# Dual_H-Bridge_Block.net
KiCad netlist of a schematic drawn in EAGLE
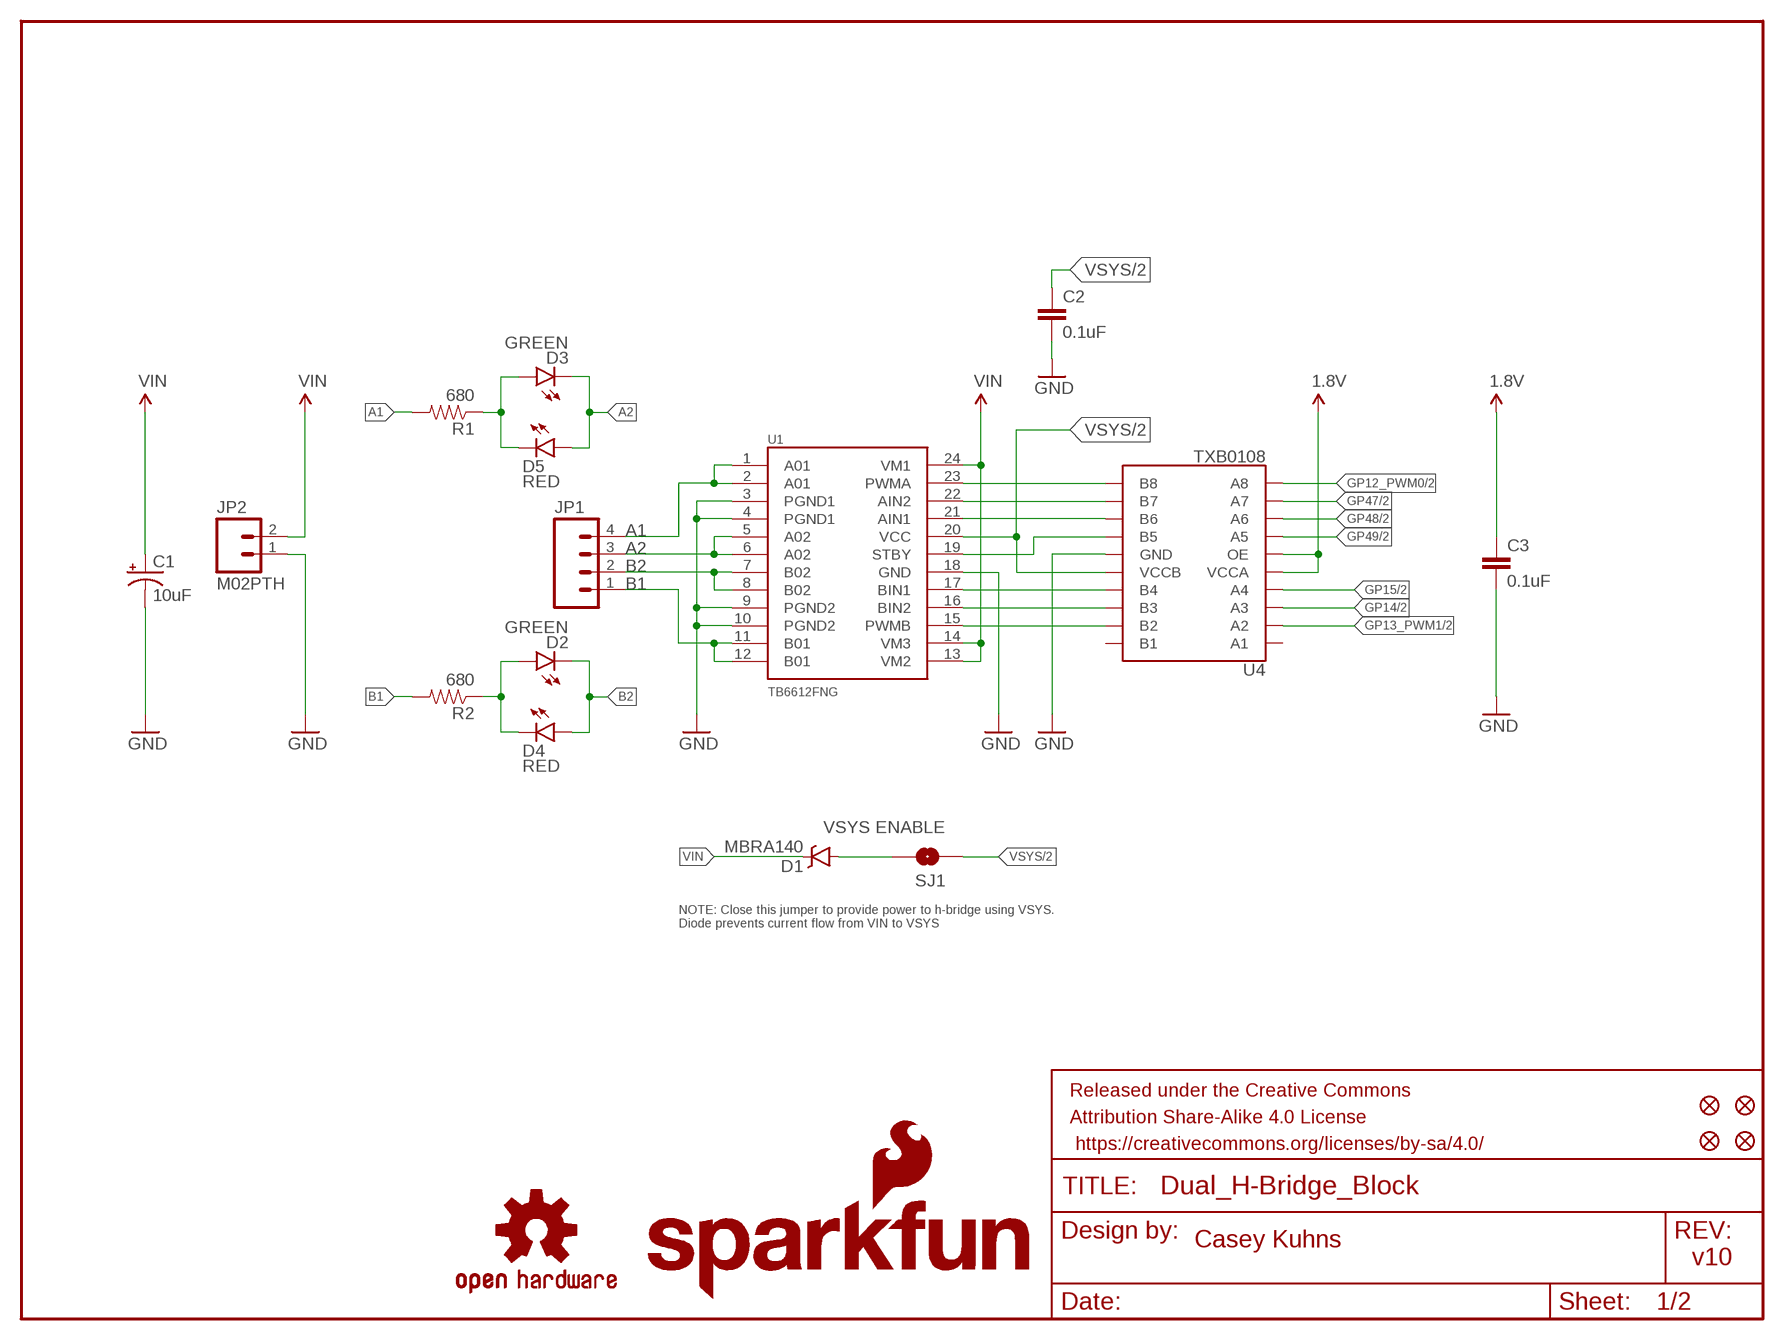
[diagram p0: schematic, sheet 1]
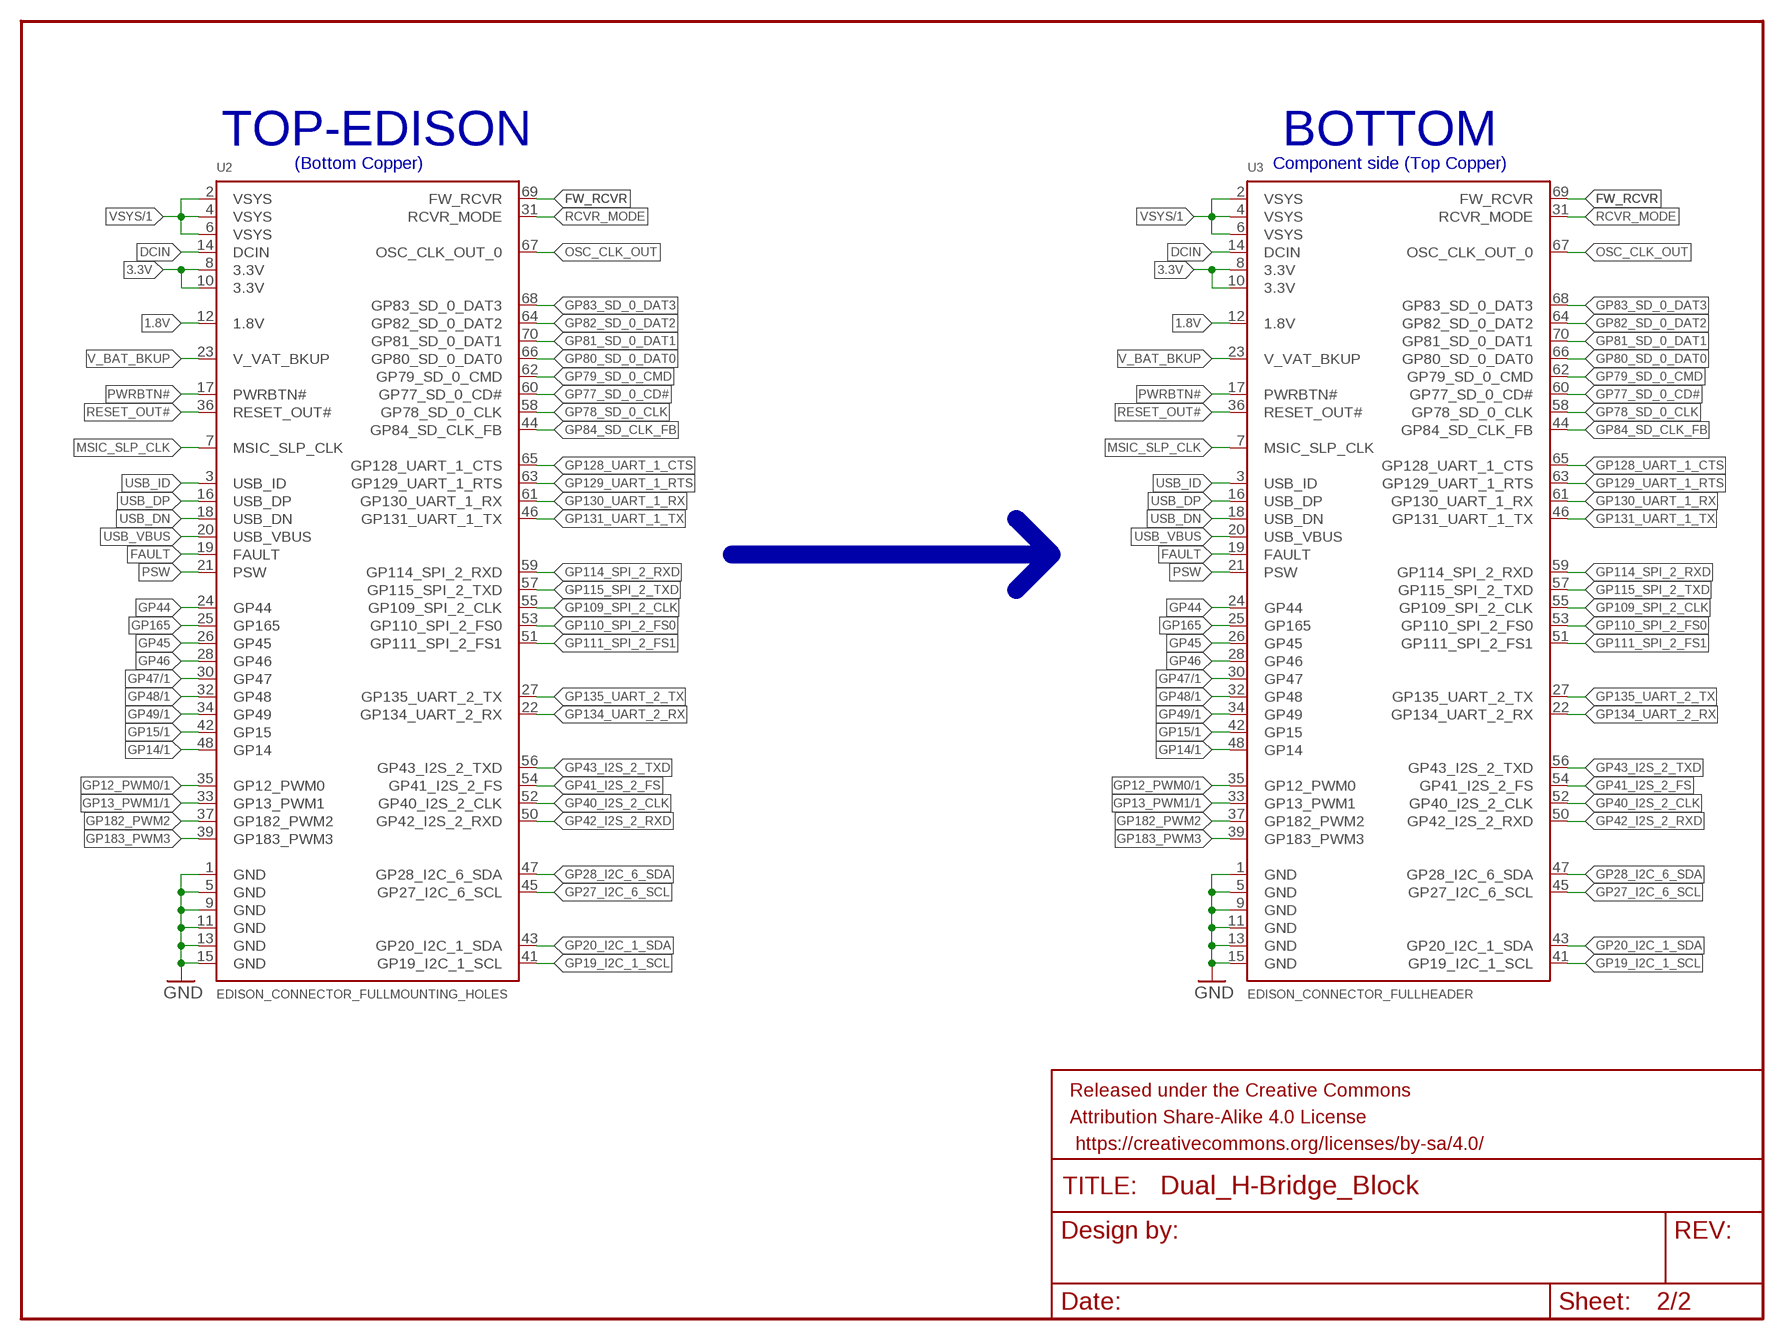
[diagram p1: schematic, sheet 2]

(export (version "E")
  (design (tool "Eeschema 10.0.6"))
  (components
    (comp (ref "FRAME2")
      (value "FRAME-LETTER")
      (footprint "eagle-import:CREATIVE_COMMONS")
      (libsource (lib "eagle-import") (part "FRAME-LETTER"))
    )
    (comp (ref "U2")
      (value "EDISON_CONNECTOR_FULLMOUNTING_HOLES")
      (footprint "eagle-import:EDISON_DAUGHTER")
      (libsource (lib "eagle-import") (part "EDISON_CONNECTOR_FULLMOUNTING_HOLES"))
    )
    (comp (ref "U3")
      (value "EDISON_CONNECTOR_FULLHEADER")
      (footprint "eagle-import:DF40C-70DP-0.4(51)")
      (libsource (lib "eagle-import") (part "EDISON_CONNECTOR_FULLHEADER"))
    )
    (comp (ref "C1")
      (value "10uF")
      (footprint "eagle-import:EIA3216")
      (libsource (lib "eagle-import") (part "10UF-16V-10%(TANT)"))
    )
    (comp (ref "C2")
      (value "0.1uF")
      (footprint "eagle-import:0603-CAP")
      (libsource (lib "eagle-import") (part "0.1UF-25V(+80/-20%)(0603)"))
    )
    (comp (ref "C3")
      (value "0.1uF")
      (footprint "eagle-import:0603-CAP")
      (libsource (lib "eagle-import") (part "0.1UF-25V(+80/-20%)(0603)"))
    )
    (comp (ref "D1")
      (value "MBRA140")
      (footprint "eagle-import:SMA-DIODE")
      (libsource (lib "eagle-import") (part "DIODE-SCHOTTKY-MBRA140"))
    )
    (comp (ref "D2")
      (value "GREEN")
      (footprint "eagle-import:LED-0603")
      (libsource (lib "eagle-import") (part "LED-GREEN0603"))
    )
    (comp (ref "D3")
      (value "GREEN")
      (footprint "eagle-import:LED-0603")
      (libsource (lib "eagle-import") (part "LED-GREEN0603"))
    )
    (comp (ref "D4")
      (value "RED")
      (footprint "eagle-import:LED-0603")
      (libsource (lib "eagle-import") (part "LED-RED0603"))
    )
    (comp (ref "D5")
      (value "RED")
      (footprint "eagle-import:LED-0603")
      (libsource (lib "eagle-import") (part "LED-RED0603"))
    )
    (comp (ref "FID1")
      (value "FIDUCIAL1X2")
      (footprint "eagle-import:FIDUCIAL-1X2")
      (libsource (lib "eagle-import") (part "FIDUCIAL1X2"))
    )
    (comp (ref "FID2")
      (value "FIDUCIAL1X2")
      (footprint "eagle-import:FIDUCIAL-1X2")
      (libsource (lib "eagle-import") (part "FIDUCIAL1X2"))
    )
    (comp (ref "FID3")
      (value "FIDUCIAL1X2")
      (footprint "eagle-import:FIDUCIAL-1X2")
      (libsource (lib "eagle-import") (part "FIDUCIAL1X2"))
    )
    (comp (ref "FID4")
      (value "FIDUCIAL1X2")
      (footprint "eagle-import:FIDUCIAL-1X2")
      (libsource (lib "eagle-import") (part "FIDUCIAL1X2"))
    )
    (comp (ref "FRAME1")
      (value "FRAME-LETTER")
      (footprint "eagle-import:CREATIVE_COMMONS")
      (libsource (lib "eagle-import") (part "FRAME-LETTER"))
    )
    (comp (ref "JP1")
      (value "M04PTH")
      (footprint "eagle-import:1X04")
      (libsource (lib "eagle-import") (part "M04PTH"))
    )
    (comp (ref "JP2")
      (value "M02PTH")
      (footprint "eagle-import:1X02")
      (libsource (lib "eagle-import") (part "M02PTH"))
    )
    (comp (ref "LOGO1")
      (value "OSHW-LOGOS")
      (footprint "eagle-import:OSHW-LOGO-S")
      (libsource (lib "eagle-import") (part "OSHW-LOGOS"))
    )
    (comp (ref "LOGO4")
      (value "SFE_LOGO_NAME_FLAME.1_INCH")
      (footprint "eagle-import:SFE_LOGO_NAME_FLAME_.1")
      (libsource (lib "eagle-import") (part "SFE_LOGO_NAME_FLAME.1_INCH"))
    )
    (comp (ref "R1")
      (value "680")
      (footprint "eagle-import:0603-RES")
      (libsource (lib "eagle-import") (part "680OHM1/10W5%(0603)"))
    )
    (comp (ref "R2")
      (value "680")
      (footprint "eagle-import:0603-RES")
      (libsource (lib "eagle-import") (part "680OHM1/10W5%(0603)"))
    )
    (comp (ref "SJ1")
      (value "VSYS ENABLE")
      (footprint "eagle-import:PAD-JUMPER-2-NO_YES_SILK")
      (libsource (lib "eagle-import") (part "JUMPER-PAD-2-NOYES_SILK"))
    )
    (comp (ref "U1")
      (value "TB6612FNG")
      (footprint "eagle-import:SSOP24")
      (libsource (lib "eagle-import") (part "TB6621FNG"))
    )
    (comp (ref "U4")
      (value "TXB0108")
      (footprint "eagle-import:UFDFN-20")
      (libsource (lib "eagle-import") (part "TXB0108"))
    )
  )
  (nets
    (net (code "1") (name "1.8V") (class "Default")
      (node (ref "C3") (pin "1") (pinfunction "1_1") (pintype "passive"))
      (node (ref "U2") (pin "12") (pinfunction "1.8V_12") (pintype "bidirectional"))
      (node (ref "U3") (pin "12") (pinfunction "1.8V_12") (pintype "bidirectional"))
      (node (ref "U4") (pin "5") (pinfunction "VCCA_5") (pintype "bidirectional"))
      (node (ref "U4") (pin "6") (pinfunction "OE_6") (pintype "bidirectional"))
    )
    (net (code "2") (name "3.3V") (class "Default")
      (node (ref "U2") (pin "10") (pinfunction "3.3V_10") (pintype "bidirectional"))
      (node (ref "U2") (pin "8") (pinfunction "3.3V_8") (pintype "bidirectional"))
      (node (ref "U3") (pin "10") (pinfunction "3.3V_10") (pintype "bidirectional"))
      (node (ref "U3") (pin "8") (pinfunction "3.3V_8") (pintype "bidirectional"))
    )
    (net (code "3") (name "A1") (class "Default")
      (node (ref "JP1") (pin "4") (pinfunction "4_4") (pintype "passive"))
      (node (ref "R1") (pin "2") (pinfunction "2_2") (pintype "passive"))
      (node (ref "U1") (pin "1") (pinfunction "A01_1") (pintype "bidirectional"))
      (node (ref "U1") (pin "2") (pinfunction "A01_2") (pintype "bidirectional"))
    )
    (net (code "4") (name "A2") (class "Default")
      (node (ref "D3") (pin "C") (pinfunction "C_C") (pintype "passive"))
      (node (ref "D5") (pin "A") (pinfunction "A_A") (pintype "passive"))
      (node (ref "JP1") (pin "3") (pinfunction "3_3") (pintype "passive"))
      (node (ref "U1") (pin "5") (pinfunction "A02_5") (pintype "bidirectional"))
      (node (ref "U1") (pin "6") (pinfunction "A02_6") (pintype "bidirectional"))
    )
    (net (code "5") (name "B1") (class "Default")
      (node (ref "JP1") (pin "1") (pinfunction "1_1") (pintype "passive"))
      (node (ref "R2") (pin "2") (pinfunction "2_2") (pintype "passive"))
      (node (ref "U1") (pin "11") (pinfunction "B01_11") (pintype "bidirectional"))
      (node (ref "U1") (pin "12") (pinfunction "B01_12") (pintype "bidirectional"))
    )
    (net (code "6") (name "B2") (class "Default")
      (node (ref "D2") (pin "C") (pinfunction "C_C") (pintype "passive"))
      (node (ref "D4") (pin "A") (pinfunction "A_A") (pintype "passive"))
      (node (ref "JP1") (pin "2") (pinfunction "2_2") (pintype "passive"))
      (node (ref "U1") (pin "7") (pinfunction "B02_7") (pintype "bidirectional"))
      (node (ref "U1") (pin "8") (pinfunction "B02_8") (pintype "bidirectional"))
    )
    (net (code "7") (name "DCIN") (class "Default")
      (node (ref "U2") (pin "14") (pinfunction "DCIN_14") (pintype "bidirectional"))
      (node (ref "U3") (pin "14") (pinfunction "DCIN_14") (pintype "bidirectional"))
    )
    (net (code "8") (name "FAULT") (class "Default")
      (node (ref "U2") (pin "19") (pinfunction "FAULT_19") (pintype "bidirectional"))
      (node (ref "U3") (pin "19") (pinfunction "FAULT_19") (pintype "bidirectional"))
    )
    (net (code "9") (name "FW_RCVR") (class "Default")
      (node (ref "U2") (pin "69") (pinfunction "FW_RCVR_69") (pintype "bidirectional"))
      (node (ref "U3") (pin "69") (pinfunction "FW_RCVR_69") (pintype "bidirectional"))
    )
    (net (code "10") (name "GND") (class "Default")
      (node (ref "C1") (pin "C") (pinfunction "-_C") (pintype "passive"))
      (node (ref "C2") (pin "2") (pinfunction "2_2") (pintype "passive"))
      (node (ref "C3") (pin "2") (pinfunction "2_2") (pintype "passive"))
      (node (ref "JP2") (pin "1") (pinfunction "1_1") (pintype "passive"))
      (node (ref "U1") (pin "10") (pinfunction "PGND2_10") (pintype "bidirectional"))
      (node (ref "U1") (pin "18") (pinfunction "GND_18") (pintype "bidirectional"))
      (node (ref "U1") (pin "3") (pinfunction "PGND1_3") (pintype "bidirectional"))
      (node (ref "U1") (pin "4") (pinfunction "PGND1_4") (pintype "bidirectional"))
      (node (ref "U1") (pin "9") (pinfunction "PGND2_9") (pintype "bidirectional"))
      (node (ref "U2") (pin "1") (pinfunction "GND_1") (pintype "bidirectional"))
      (node (ref "U2") (pin "11") (pinfunction "GND_11") (pintype "bidirectional"))
      (node (ref "U2") (pin "13") (pinfunction "GND_13") (pintype "bidirectional"))
      (node (ref "U2") (pin "15") (pinfunction "GND_15") (pintype "bidirectional"))
      (node (ref "U2") (pin "5") (pinfunction "GND_5") (pintype "bidirectional"))
      (node (ref "U2") (pin "9") (pinfunction "GND_9") (pintype "bidirectional"))
      (node (ref "U3") (pin "1") (pinfunction "GND_1") (pintype "bidirectional"))
      (node (ref "U3") (pin "11") (pinfunction "GND_11") (pintype "bidirectional"))
      (node (ref "U3") (pin "13") (pinfunction "GND_13") (pintype "bidirectional"))
      (node (ref "U3") (pin "15") (pinfunction "GND_15") (pintype "bidirectional"))
      (node (ref "U3") (pin "5") (pinfunction "GND_5") (pintype "bidirectional"))
      (node (ref "U3") (pin "9") (pinfunction "GND_9") (pintype "bidirectional"))
      (node (ref "U4") (pin "15") (pinfunction "GND_15") (pintype "bidirectional"))
    )
    (net (code "11") (name "GP12_PWM0") (class "Default")
      (node (ref "U2") (pin "35") (pinfunction "GP12_PWM0_35") (pintype "bidirectional"))
      (node (ref "U3") (pin "35") (pinfunction "GP12_PWM0_35") (pintype "bidirectional"))
      (node (ref "U4") (pin "10") (pinfunction "A8_10") (pintype "bidirectional"))
    )
    (net (code "12") (name "GP13_PWM1") (class "Default")
      (node (ref "U2") (pin "33") (pinfunction "GP13_PWM1_33") (pintype "bidirectional"))
      (node (ref "U3") (pin "33") (pinfunction "GP13_PWM1_33") (pintype "bidirectional"))
      (node (ref "U4") (pin "2") (pinfunction "A2_2") (pintype "bidirectional"))
    )
    (net (code "13") (name "GP14") (class "Default")
      (node (ref "U2") (pin "48") (pinfunction "GP14_48") (pintype "bidirectional"))
      (node (ref "U3") (pin "48") (pinfunction "GP14_48") (pintype "bidirectional"))
      (node (ref "U4") (pin "3") (pinfunction "A3_3") (pintype "bidirectional"))
    )
    (net (code "14") (name "GP15") (class "Default")
      (node (ref "U2") (pin "42") (pinfunction "GP15_42") (pintype "bidirectional"))
      (node (ref "U3") (pin "42") (pinfunction "GP15_42") (pintype "bidirectional"))
      (node (ref "U4") (pin "4") (pinfunction "A4_4") (pintype "bidirectional"))
    )
    (net (code "15") (name "GP19_I2C_1_SCL") (class "Default")
      (node (ref "U2") (pin "41") (pinfunction "GP19_I2C_1_SCL_41") (pintype "bidirectional"))
      (node (ref "U3") (pin "41") (pinfunction "GP19_I2C_1_SCL_41") (pintype "bidirectional"))
    )
    (net (code "16") (name "GP20_I2C_1_SDA") (class "Default")
      (node (ref "U2") (pin "43") (pinfunction "GP20_I2C_1_SDA_43") (pintype "bidirectional"))
      (node (ref "U3") (pin "43") (pinfunction "GP20_I2C_1_SDA_43") (pintype "bidirectional"))
    )
    (net (code "17") (name "GP27_I2C_6_SCL") (class "Default")
      (node (ref "U2") (pin "45") (pinfunction "GP27_I2C_6_SCL_45") (pintype "bidirectional"))
      (node (ref "U3") (pin "45") (pinfunction "GP27_I2C_6_SCL_45") (pintype "bidirectional"))
    )
    (net (code "18") (name "GP28_I2C_6_SDA") (class "Default")
      (node (ref "U2") (pin "47") (pinfunction "GP28_I2C_6_SDA_47") (pintype "bidirectional"))
      (node (ref "U3") (pin "47") (pinfunction "GP28_I2C_6_SDA_47") (pintype "bidirectional"))
    )
    (net (code "19") (name "GP40_I2S_2_CLK") (class "Default")
      (node (ref "U2") (pin "52") (pinfunction "GP40_I2S_2_CLK_52") (pintype "bidirectional"))
      (node (ref "U3") (pin "52") (pinfunction "GP40_I2S_2_CLK_52") (pintype "bidirectional"))
    )
    (net (code "20") (name "GP41_I2S_2_FS") (class "Default")
      (node (ref "U2") (pin "54") (pinfunction "GP41_I2S_2_FS_54") (pintype "bidirectional"))
      (node (ref "U3") (pin "54") (pinfunction "GP41_I2S_2_FS_54") (pintype "bidirectional"))
    )
    (net (code "21") (name "GP42_I2S_2_RXD") (class "Default")
      (node (ref "U2") (pin "50") (pinfunction "GP42_I2S_2_RXD_50") (pintype "bidirectional"))
      (node (ref "U3") (pin "50") (pinfunction "GP42_I2S_2_RXD_50") (pintype "bidirectional"))
    )
    (net (code "22") (name "GP43_I2S_2_TXD") (class "Default")
      (node (ref "U2") (pin "56") (pinfunction "GP43_I2S_2_TXD_56") (pintype "bidirectional"))
      (node (ref "U3") (pin "56") (pinfunction "GP43_I2S_2_TXD_56") (pintype "bidirectional"))
    )
    (net (code "23") (name "GP44") (class "Default")
      (node (ref "U2") (pin "24") (pinfunction "GP44_24") (pintype "bidirectional"))
      (node (ref "U3") (pin "24") (pinfunction "GP44_24") (pintype "bidirectional"))
    )
    (net (code "24") (name "GP45") (class "Default")
      (node (ref "U2") (pin "26") (pinfunction "GP45_26") (pintype "bidirectional"))
      (node (ref "U3") (pin "26") (pinfunction "GP45_26") (pintype "bidirectional"))
    )
    (net (code "25") (name "GP46") (class "Default")
      (node (ref "U2") (pin "28") (pinfunction "GP46_28") (pintype "bidirectional"))
      (node (ref "U3") (pin "28") (pinfunction "GP46_28") (pintype "bidirectional"))
    )
    (net (code "26") (name "GP47") (class "Default")
      (node (ref "U2") (pin "30") (pinfunction "GP47_30") (pintype "bidirectional"))
      (node (ref "U3") (pin "30") (pinfunction "GP47_30") (pintype "bidirectional"))
      (node (ref "U4") (pin "9") (pinfunction "A7_9") (pintype "bidirectional"))
    )
    (net (code "27") (name "GP48") (class "Default")
      (node (ref "U2") (pin "32") (pinfunction "GP48_32") (pintype "bidirectional"))
      (node (ref "U3") (pin "32") (pinfunction "GP48_32") (pintype "bidirectional"))
      (node (ref "U4") (pin "8") (pinfunction "A6_8") (pintype "bidirectional"))
    )
    (net (code "28") (name "GP49") (class "Default")
      (node (ref "U2") (pin "34") (pinfunction "GP49_34") (pintype "bidirectional"))
      (node (ref "U3") (pin "34") (pinfunction "GP49_34") (pintype "bidirectional"))
      (node (ref "U4") (pin "7") (pinfunction "A5_7") (pintype "bidirectional"))
    )
    (net (code "29") (name "GP77_SD_0_CD#") (class "Default")
      (node (ref "U2") (pin "60") (pinfunction "GP77_SD_0_CD#_60") (pintype "bidirectional"))
      (node (ref "U3") (pin "60") (pinfunction "GP77_SD_0_CD#_60") (pintype "bidirectional"))
    )
    (net (code "30") (name "GP78_SD_0_CLK") (class "Default")
      (node (ref "U2") (pin "58") (pinfunction "GP78_SD_0_CLK_58") (pintype "bidirectional"))
      (node (ref "U3") (pin "58") (pinfunction "GP78_SD_0_CLK_58") (pintype "bidirectional"))
    )
    (net (code "31") (name "GP79_SD_0_CMD") (class "Default")
      (node (ref "U2") (pin "62") (pinfunction "GP79_SD_0_CMD_62") (pintype "bidirectional"))
      (node (ref "U3") (pin "62") (pinfunction "GP79_SD_0_CMD_62") (pintype "bidirectional"))
    )
    (net (code "32") (name "GP80_SD_0_DAT0") (class "Default")
      (node (ref "U2") (pin "66") (pinfunction "GP80_SD_0_DAT0_66") (pintype "bidirectional"))
      (node (ref "U3") (pin "66") (pinfunction "GP80_SD_0_DAT0_66") (pintype "bidirectional"))
    )
    (net (code "33") (name "GP81_SD_0_DAT1") (class "Default")
      (node (ref "U2") (pin "70") (pinfunction "GP81_SD_0_DAT1_70") (pintype "bidirectional"))
      (node (ref "U3") (pin "70") (pinfunction "GP81_SD_0_DAT1_70") (pintype "bidirectional"))
    )
    (net (code "34") (name "GP82_SD_0_DAT2") (class "Default")
      (node (ref "U2") (pin "64") (pinfunction "GP82_SD_0_DAT2_64") (pintype "bidirectional"))
      (node (ref "U3") (pin "64") (pinfunction "GP82_SD_0_DAT2_64") (pintype "bidirectional"))
    )
    (net (code "35") (name "GP83_SD_0_DAT3") (class "Default")
      (node (ref "U2") (pin "68") (pinfunction "GP83_SD_0_DAT3_68") (pintype "bidirectional"))
      (node (ref "U3") (pin "68") (pinfunction "GP83_SD_0_DAT3_68") (pintype "bidirectional"))
    )
    (net (code "36") (name "GP84_SD_CLK_FB") (class "Default")
      (node (ref "U2") (pin "44") (pinfunction "GP84_SD_CLK_FB_44") (pintype "bidirectional"))
      (node (ref "U3") (pin "44") (pinfunction "GP84_SD_CLK_FB_44") (pintype "bidirectional"))
    )
    (net (code "37") (name "GP109_SPI_2_CLK") (class "Default")
      (node (ref "U2") (pin "55") (pinfunction "GP109_SPI_2_CLK_55") (pintype "bidirectional"))
      (node (ref "U3") (pin "55") (pinfunction "GP109_SPI_2_CLK_55") (pintype "bidirectional"))
    )
    (net (code "38") (name "GP110_SPI_2_FS0") (class "Default")
      (node (ref "U2") (pin "53") (pinfunction "GP110_SPI_2_FS0_53") (pintype "bidirectional"))
      (node (ref "U3") (pin "53") (pinfunction "GP110_SPI_2_FS0_53") (pintype "bidirectional"))
    )
    (net (code "39") (name "GP111_SPI_2_FS1") (class "Default")
      (node (ref "U2") (pin "51") (pinfunction "GP111_SPI_2_FS1_51") (pintype "bidirectional"))
      (node (ref "U3") (pin "51") (pinfunction "GP111_SPI_2_FS1_51") (pintype "bidirectional"))
    )
    (net (code "40") (name "GP114_SPI_2_RXD") (class "Default")
      (node (ref "U2") (pin "59") (pinfunction "GP114_SPI_2_RXD_59") (pintype "bidirectional"))
      (node (ref "U3") (pin "59") (pinfunction "GP114_SPI_2_RXD_59") (pintype "bidirectional"))
    )
    (net (code "41") (name "GP115_SPI_2_TXD") (class "Default")
      (node (ref "U2") (pin "57") (pinfunction "GP115_SPI_2_TXD_57") (pintype "bidirectional"))
      (node (ref "U3") (pin "57") (pinfunction "GP115_SPI_2_TXD_57") (pintype "bidirectional"))
    )
    (net (code "42") (name "GP128_UART_1_CTS") (class "Default")
      (node (ref "U2") (pin "65") (pinfunction "GP128_UART_1_CTS_65") (pintype "bidirectional"))
      (node (ref "U3") (pin "65") (pinfunction "GP128_UART_1_CTS_65") (pintype "bidirectional"))
    )
    (net (code "43") (name "GP129_UART_1_RTS") (class "Default")
      (node (ref "U2") (pin "63") (pinfunction "GP129_UART_1_RTS_63") (pintype "bidirectional"))
      (node (ref "U3") (pin "63") (pinfunction "GP129_UART_1_RTS_63") (pintype "bidirectional"))
    )
    (net (code "44") (name "GP130_UART_1_RX") (class "Default")
      (node (ref "U2") (pin "61") (pinfunction "GP130_UART_1_RX_61") (pintype "bidirectional"))
      (node (ref "U3") (pin "61") (pinfunction "GP130_UART_1_RX_61") (pintype "bidirectional"))
    )
    (net (code "45") (name "GP131_UART_1_TX") (class "Default")
      (node (ref "U2") (pin "46") (pinfunction "GP131_UART_1_TX_46") (pintype "bidirectional"))
      (node (ref "U3") (pin "46") (pinfunction "GP131_UART_1_TX_46") (pintype "bidirectional"))
    )
    (net (code "46") (name "GP134_UART_2_RX") (class "Default")
      (node (ref "U2") (pin "22") (pinfunction "GP134_UART_2_RX_22") (pintype "bidirectional"))
      (node (ref "U3") (pin "22") (pinfunction "GP134_UART_2_RX_22") (pintype "bidirectional"))
    )
    (net (code "47") (name "GP135_UART_2_TX") (class "Default")
      (node (ref "U2") (pin "27") (pinfunction "GP135_UART_2_TX_27") (pintype "bidirectional"))
      (node (ref "U3") (pin "27") (pinfunction "GP135_UART_2_TX_27") (pintype "bidirectional"))
    )
    (net (code "48") (name "GP165") (class "Default")
      (node (ref "U2") (pin "25") (pinfunction "GP165_25") (pintype "bidirectional"))
      (node (ref "U3") (pin "25") (pinfunction "GP165_25") (pintype "bidirectional"))
    )
    (net (code "49") (name "GP182_PWM2") (class "Default")
      (node (ref "U2") (pin "37") (pinfunction "GP182_PWM2_37") (pintype "bidirectional"))
      (node (ref "U3") (pin "37") (pinfunction "GP182_PWM2_37") (pintype "bidirectional"))
    )
    (net (code "50") (name "GP183_PWM3") (class "Default")
      (node (ref "U2") (pin "39") (pinfunction "GP183_PWM3_39") (pintype "bidirectional"))
      (node (ref "U3") (pin "39") (pinfunction "GP183_PWM3_39") (pintype "bidirectional"))
    )
    (net (code "51") (name "MSIC_SLP_CLK") (class "Default")
      (node (ref "U2") (pin "7") (pinfunction "MSIC_SLP_CLK_7") (pintype "bidirectional"))
      (node (ref "U3") (pin "7") (pinfunction "MSIC_SLP_CLK_7") (pintype "bidirectional"))
    )
    (net (code "52") (name "Net-(D1-PadA)") (class "Default")
      (node (ref "D1") (pin "A") (pinfunction "A_A") (pintype "passive"))
      (node (ref "SJ1") (pin "2") (pinfunction "2_2") (pintype "passive"))
    )
    (net (code "53") (name "Net-(D2-PadA)") (class "Default")
      (node (ref "D2") (pin "A") (pinfunction "A_A") (pintype "passive"))
      (node (ref "D4") (pin "C") (pinfunction "C_C") (pintype "passive"))
      (node (ref "R2") (pin "1") (pinfunction "1_1") (pintype "passive"))
    )
    (net (code "54") (name "Net-(D3-PadA)") (class "Default")
      (node (ref "D3") (pin "A") (pinfunction "A_A") (pintype "passive"))
      (node (ref "D5") (pin "C") (pinfunction "C_C") (pintype "passive"))
      (node (ref "R1") (pin "1") (pinfunction "1_1") (pintype "passive"))
    )
    (net (code "55") (name "Net-(U1-AIN1)") (class "Default")
      (node (ref "U1") (pin "21") (pinfunction "AIN1_21") (pintype "bidirectional"))
      (node (ref "U4") (pin "13") (pinfunction "B6_13") (pintype "bidirectional"))
    )
    (net (code "56") (name "Net-(U1-AIN2)") (class "Default")
      (node (ref "U1") (pin "22") (pinfunction "AIN2_22") (pintype "bidirectional"))
      (node (ref "U4") (pin "12") (pinfunction "B7_12") (pintype "bidirectional"))
    )
    (net (code "57") (name "Net-(U1-BIN1)") (class "Default")
      (node (ref "U1") (pin "17") (pinfunction "BIN1_17") (pintype "bidirectional"))
      (node (ref "U4") (pin "17") (pinfunction "B4_17") (pintype "bidirectional"))
    )
    (net (code "58") (name "Net-(U1-BIN2)") (class "Default")
      (node (ref "U1") (pin "16") (pinfunction "BIN2_16") (pintype "bidirectional"))
      (node (ref "U4") (pin "18") (pinfunction "B3_18") (pintype "bidirectional"))
    )
    (net (code "59") (name "Net-(U1-PWMA)") (class "Default")
      (node (ref "U1") (pin "23") (pinfunction "PWMA_23") (pintype "bidirectional"))
      (node (ref "U4") (pin "11") (pinfunction "B8_11") (pintype "bidirectional"))
    )
    (net (code "60") (name "Net-(U1-PWMB)") (class "Default")
      (node (ref "U1") (pin "15") (pinfunction "PWMB_15") (pintype "bidirectional"))
      (node (ref "U4") (pin "19") (pinfunction "B2_19") (pintype "bidirectional"))
    )
    (net (code "61") (name "Net-(U1-STBY)") (class "Default")
      (node (ref "U1") (pin "19") (pinfunction "STBY_19") (pintype "bidirectional"))
      (node (ref "U4") (pin "14") (pinfunction "B5_14") (pintype "bidirectional"))
    )
    (net (code "62") (name "OSC_CLK_OUT") (class "Default")
      (node (ref "U2") (pin "67") (pinfunction "OSC_CLK_OUT_0_67") (pintype "bidirectional"))
      (node (ref "U3") (pin "67") (pinfunction "OSC_CLK_OUT_0_67") (pintype "bidirectional"))
    )
    (net (code "63") (name "PSW") (class "Default")
      (node (ref "U2") (pin "21") (pinfunction "PSW_21") (pintype "bidirectional"))
      (node (ref "U3") (pin "21") (pinfunction "PSW_21") (pintype "bidirectional"))
    )
    (net (code "64") (name "PWRBTN#") (class "Default")
      (node (ref "U2") (pin "17") (pinfunction "PWRBTN#_17") (pintype "bidirectional"))
      (node (ref "U3") (pin "17") (pinfunction "PWRBTN#_17") (pintype "bidirectional"))
    )
    (net (code "65") (name "RCVR_MODE") (class "Default")
      (node (ref "U2") (pin "31") (pinfunction "RCVR_MODE_31") (pintype "bidirectional"))
      (node (ref "U3") (pin "31") (pinfunction "RCVR_MODE_31") (pintype "bidirectional"))
    )
    (net (code "66") (name "RESET_OUT#") (class "Default")
      (node (ref "U2") (pin "36") (pinfunction "RESET_OUT#_36") (pintype "bidirectional"))
      (node (ref "U3") (pin "36") (pinfunction "RESET_OUT#_36") (pintype "bidirectional"))
    )
    (net (code "67") (name "USB_DN") (class "Default")
      (node (ref "U2") (pin "18") (pinfunction "USB_DN_18") (pintype "bidirectional"))
      (node (ref "U3") (pin "18") (pinfunction "USB_DN_18") (pintype "bidirectional"))
    )
    (net (code "68") (name "USB_DP") (class "Default")
      (node (ref "U2") (pin "16") (pinfunction "USB_DP_16") (pintype "bidirectional"))
      (node (ref "U3") (pin "16") (pinfunction "USB_DP_16") (pintype "bidirectional"))
    )
    (net (code "69") (name "USB_ID") (class "Default")
      (node (ref "U2") (pin "3") (pinfunction "USB_ID_3") (pintype "bidirectional"))
      (node (ref "U3") (pin "3") (pinfunction "USB_ID_3") (pintype "bidirectional"))
    )
    (net (code "70") (name "USB_VBUS") (class "Default")
      (node (ref "U2") (pin "20") (pinfunction "USB_VBUS_20") (pintype "bidirectional"))
      (node (ref "U3") (pin "20") (pinfunction "USB_VBUS_20") (pintype "bidirectional"))
    )
    (net (code "71") (name "VIN") (class "Default")
      (node (ref "C1") (pin "A") (pinfunction "+_A") (pintype "passive"))
      (node (ref "D1") (pin "C") (pinfunction "C_C") (pintype "passive"))
      (node (ref "JP2") (pin "2") (pinfunction "2_2") (pintype "passive"))
      (node (ref "U1") (pin "13") (pinfunction "VM2_13") (pintype "bidirectional"))
      (node (ref "U1") (pin "14") (pinfunction "VM3_14") (pintype "bidirectional"))
      (node (ref "U1") (pin "24") (pinfunction "VM1_24") (pintype "bidirectional"))
    )
    (net (code "72") (name "VSYS") (class "Default")
      (node (ref "C2") (pin "1") (pinfunction "1_1") (pintype "passive"))
      (node (ref "SJ1") (pin "1") (pinfunction "1_1") (pintype "passive"))
      (node (ref "U1") (pin "20") (pinfunction "VCC_20") (pintype "bidirectional"))
      (node (ref "U2") (pin "2") (pinfunction "VSYS_2") (pintype "bidirectional"))
      (node (ref "U2") (pin "4") (pinfunction "VSYS_4") (pintype "bidirectional"))
      (node (ref "U2") (pin "6") (pinfunction "VSYS_6") (pintype "bidirectional"))
      (node (ref "U3") (pin "2") (pinfunction "VSYS_2") (pintype "bidirectional"))
      (node (ref "U3") (pin "4") (pinfunction "VSYS_4") (pintype "bidirectional"))
      (node (ref "U3") (pin "6") (pinfunction "VSYS_6") (pintype "bidirectional"))
      (node (ref "U4") (pin "16") (pinfunction "VCCB_16") (pintype "bidirectional"))
    )
    (net (code "73") (name "V_BAT_BKUP") (class "Default")
      (node (ref "U2") (pin "23") (pinfunction "V_VAT_BKUP_23") (pintype "bidirectional"))
      (node (ref "U3") (pin "23") (pinfunction "V_VAT_BKUP_23") (pintype "bidirectional"))
    )
    (net (code "74") (name "unconnected-(U4-A1-Pad1)") (class "Default")
      (node (ref "U4") (pin "1") (pinfunction "A1_1") (pintype "bidirectional"))
    )
    (net (code "75") (name "unconnected-(U4-B1-Pad20)") (class "Default")
      (node (ref "U4") (pin "20") (pinfunction "B1_20") (pintype "bidirectional"))
    )
  )
)
